# Reg.net
KiCad netlist of a schematic drawn in EAGLE
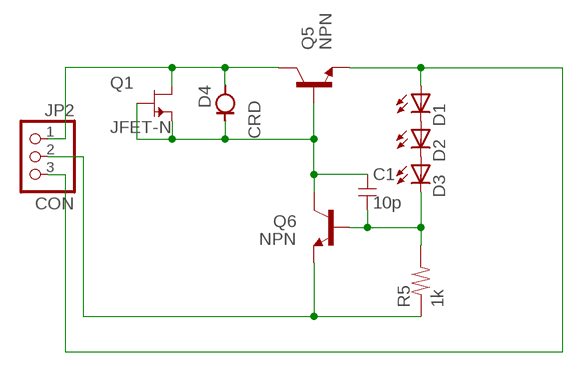
[diagram p0: schematic, sheet 1]

(export (version "E")
  (design (tool "Eeschema 10.0.6"))
  (components
    (comp (ref "C1")
      (value "10p")
      (footprint "eagle-import:1608")
      (libsource (lib "eagle-import") (part "C-1608"))
    )
    (comp (ref "D1")
      (value "LED-SMD2012")
      (footprint "eagle-import:D2012")
      (libsource (lib "eagle-import") (part "LED-SMD2012"))
    )
    (comp (ref "D2")
      (value "LED-SMD2012")
      (footprint "eagle-import:D2012")
      (libsource (lib "eagle-import") (part "LED-SMD2012"))
    )
    (comp (ref "D3")
      (value "LED-SMD2012")
      (footprint "eagle-import:D2012")
      (libsource (lib "eagle-import") (part "LED-SMD2012"))
    )
    (comp (ref "D4")
      (value "CRD")
      (footprint "eagle-import:SOD123")
      (libsource (lib "eagle-import") (part "CRD-SMD"))
    )
    (comp (ref "JP2")
      (value "CON")
      (footprint "eagle-import:1X03")
      (libsource (lib "eagle-import") (part "SW-1X3"))
    )
    (comp (ref "Q1")
      (value "JFET-N")
      (footprint "eagle-import:SC59")
      (libsource (lib "eagle-import") (part "JFET-N"))
    )
    (comp (ref "Q5")
      (value "NPN")
      (footprint "eagle-import:TO126-2")
      (libsource (lib "eagle-import") (part "NPN2SC3422-2"))
    )
    (comp (ref "Q6")
      (value "NPN")
      (footprint "eagle-import:SC59")
      (libsource (lib "eagle-import") (part "NPN2SC3325"))
    )
    (comp (ref "R5")
      (value "1k")
      (footprint "eagle-import:1608")
      (libsource (lib "eagle-import") (part "R-1608"))
    )
  )
  (nets
    (net (code "1") (name "Net-(D1-PadK)") (class "Default")
      (node (ref "D1") (pin "K") (pinfunction "K_K") (pintype "passive"))
      (node (ref "D2") (pin "A") (pinfunction "A_A") (pintype "passive"))
    )
    (net (code "2") (name "Net-(D2-PadK)") (class "Default")
      (node (ref "D2") (pin "K") (pinfunction "K_K") (pintype "passive"))
      (node (ref "D3") (pin "A") (pinfunction "A_A") (pintype "passive"))
    )
    (net (code "3") (name "Net-(D4-A)") (class "Default")
      (node (ref "D4") (pin "1") (pinfunction "A_1") (pintype "passive"))
      (node (ref "JP2") (pin "1") (pinfunction "1_1") (pintype "passive"))
      (node (ref "Q1") (pin "2") (pinfunction "D_2") (pintype "passive"))
      (node (ref "Q5") (pin "2") (pinfunction "C_2") (pintype "passive"))
    )
    (net (code "4") (name "Net-(D4-K)") (class "Default")
      (node (ref "C1") (pin "1") (pinfunction "1_1") (pintype "passive"))
      (node (ref "D4") (pin "2") (pinfunction "K_2") (pintype "passive"))
      (node (ref "Q1") (pin "1") (pinfunction "S_1") (pintype "passive"))
      (node (ref "Q1") (pin "3") (pinfunction "G_3") (pintype "passive"))
      (node (ref "Q5") (pin "3") (pinfunction "B_3") (pintype "passive"))
      (node (ref "Q6") (pin "3") (pinfunction "C_3") (pintype "passive"))
    )
    (net (code "5") (name "Net-(Q5-E)") (class "Default")
      (node (ref "D1") (pin "A") (pinfunction "A_A") (pintype "passive"))
      (node (ref "JP2") (pin "3") (pinfunction "3_3") (pintype "passive"))
      (node (ref "Q5") (pin "1") (pinfunction "E_1") (pintype "passive"))
    )
    (net (code "6") (name "Net-(Q6-B)") (class "Default")
      (node (ref "C1") (pin "2") (pinfunction "2_2") (pintype "passive"))
      (node (ref "D3") (pin "K") (pinfunction "K_K") (pintype "passive"))
      (node (ref "Q6") (pin "1") (pinfunction "B_1") (pintype "passive"))
      (node (ref "R5") (pin "2") (pinfunction "2_2") (pintype "passive"))
    )
    (net (code "7") (name "Net-(Q6-E)") (class "Default")
      (node (ref "JP2") (pin "2") (pinfunction "2_2") (pintype "passive"))
      (node (ref "Q6") (pin "2") (pinfunction "E_2") (pintype "passive"))
      (node (ref "R5") (pin "1") (pinfunction "1_1") (pintype "passive"))
    )
  )
)
